# variable_supply_module_v2.net
KiCad netlist of a schematic drawn in EAGLE
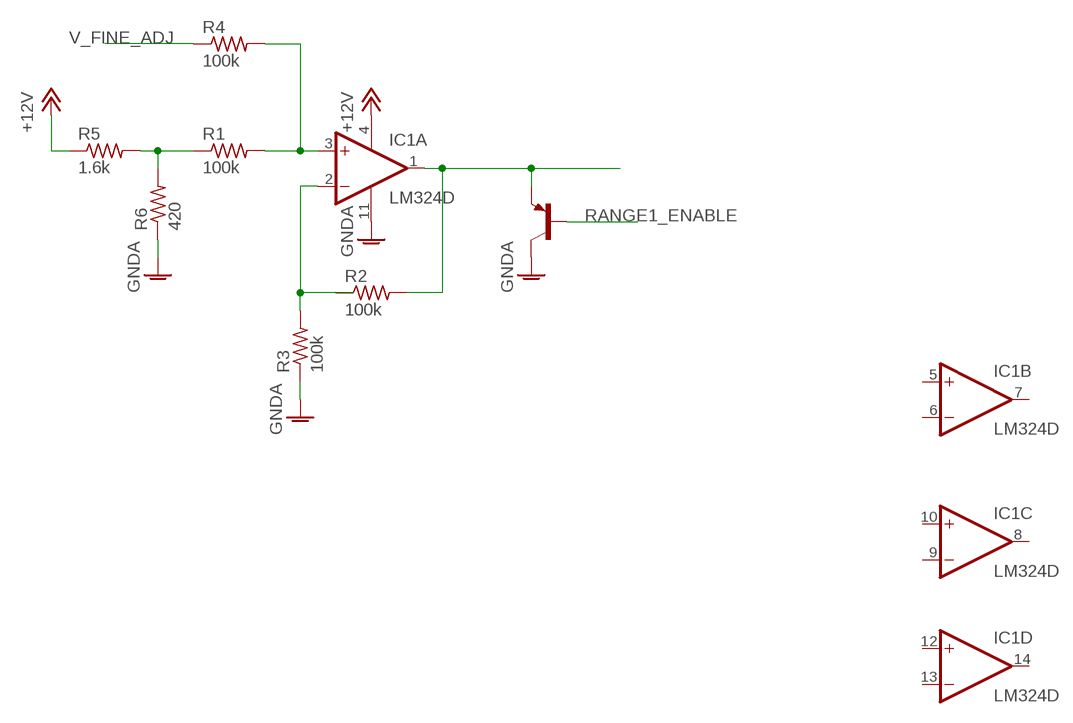
[diagram p0: schematic, sheet 1]

(export (version "E")
  (design (tool "Eeschema 10.0.6"))
  (components
    (comp (ref "IC1")
      (value "LM324D")
      (footprint "eagle-import:SO14")
      (libsource (lib "eagle-import") (part "LM324D"))
    )
    (comp (ref "R1")
      (value "100k")
      (footprint "eagle-import:M0805")
      (libsource (lib "eagle-import") (part "R-US_M0805"))
    )
    (comp (ref "R2")
      (value "100k")
      (footprint "eagle-import:M0805")
      (libsource (lib "eagle-import") (part "R-US_M0805"))
    )
    (comp (ref "R3")
      (value "100k")
      (footprint "eagle-import:M0805")
      (libsource (lib "eagle-import") (part "R-US_M0805"))
    )
    (comp (ref "R4")
      (value "100k")
      (footprint "eagle-import:M0805")
      (libsource (lib "eagle-import") (part "R-US_M0805"))
    )
    (comp (ref "R5")
      (value "1.6k")
      (footprint "eagle-import:M0805")
      (libsource (lib "eagle-import") (part "R-US_M0805"))
    )
    (comp (ref "R6")
      (value "420")
      (footprint "eagle-import:M0805")
      (libsource (lib "eagle-import") (part "R-US_M0805"))
    )
    (comp (ref "T1")
      (value "MMBT3906LT1-PNP-SOT23-BEC")
      (footprint "eagle-import:SOT23-BEC")
      (libsource (lib "eagle-import") (part "-PNP-SOT23-BECMMBT3906LT1"))
    )
  )
  (nets
    (net (code "1") (name "+12V") (class "Default")
      (node (ref "IC1") (pin "4") (pinfunction "V+_4") (pintype "power_in"))
      (node (ref "R5") (pin "1") (pinfunction "1_1") (pintype "passive"))
    )
    (net (code "2") (name "/RANGE1_ENABLE") (class "Default")
      (node (ref "T1") (pin "B") (pinfunction "B_B") (pintype "passive"))
    )
    (net (code "3") (name "/V_FINE_ADJ") (class "Default")
      (node (ref "R4") (pin "1") (pinfunction "1_1") (pintype "passive"))
    )
    (net (code "4") (name "GNDA") (class "Default")
      (node (ref "IC1") (pin "11") (pinfunction "V-_11") (pintype "power_in"))
      (node (ref "R3") (pin "1") (pinfunction "1_1") (pintype "passive"))
      (node (ref "R6") (pin "1") (pinfunction "1_1") (pintype "passive"))
      (node (ref "T1") (pin "C") (pinfunction "C_C") (pintype "passive"))
    )
    (net (code "5") (name "Net-(IC1A-+IN)") (class "Default")
      (node (ref "IC1") (pin "3") (pinfunction "+IN_3") (pintype "input"))
      (node (ref "R1") (pin "2") (pinfunction "2_2") (pintype "passive"))
      (node (ref "R4") (pin "2") (pinfunction "2_2") (pintype "passive"))
    )
    (net (code "6") (name "Net-(IC1A--IN)") (class "Default")
      (node (ref "IC1") (pin "2") (pinfunction "-IN_2") (pintype "input"))
      (node (ref "R3") (pin "2") (pinfunction "2_2") (pintype "passive"))
    )
    (net (code "7") (name "Net-(IC1A-OUT)") (class "Default")
      (node (ref "IC1") (pin "1") (pinfunction "OUT_1") (pintype "output"))
      (node (ref "R2") (pin "2") (pinfunction "2_2") (pintype "passive"))
      (node (ref "T1") (pin "E") (pinfunction "E_E") (pintype "passive"))
    )
    (net (code "8") (name "Net-(R1-Pad1)") (class "Default")
      (node (ref "R1") (pin "1") (pinfunction "1_1") (pintype "passive"))
      (node (ref "R5") (pin "2") (pinfunction "2_2") (pintype "passive"))
      (node (ref "R6") (pin "2") (pinfunction "2_2") (pintype "passive"))
    )
    (net (code "9") (name "unconnected-(IC1B-+IN-Pad5)") (class "Default")
      (node (ref "IC1") (pin "5") (pinfunction "+IN_5") (pintype "input"))
    )
    (net (code "10") (name "unconnected-(IC1B--IN-Pad6)") (class "Default")
      (node (ref "IC1") (pin "6") (pinfunction "-IN_6") (pintype "input"))
    )
    (net (code "11") (name "unconnected-(IC1B-OUT-Pad7)") (class "Default")
      (node (ref "IC1") (pin "7") (pinfunction "OUT_7") (pintype "output"))
    )
    (net (code "12") (name "unconnected-(IC1C-+IN-Pad10)") (class "Default")
      (node (ref "IC1") (pin "10") (pinfunction "+IN_10") (pintype "input"))
    )
    (net (code "13") (name "unconnected-(IC1C--IN-Pad9)") (class "Default")
      (node (ref "IC1") (pin "9") (pinfunction "-IN_9") (pintype "input"))
    )
    (net (code "14") (name "unconnected-(IC1C-OUT-Pad8)") (class "Default")
      (node (ref "IC1") (pin "8") (pinfunction "OUT_8") (pintype "output"))
    )
    (net (code "15") (name "unconnected-(IC1D-+IN-Pad12)") (class "Default")
      (node (ref "IC1") (pin "12") (pinfunction "+IN_12") (pintype "input"))
    )
    (net (code "16") (name "unconnected-(IC1D--IN-Pad13)") (class "Default")
      (node (ref "IC1") (pin "13") (pinfunction "-IN_13") (pintype "input"))
    )
    (net (code "17") (name "unconnected-(IC1D-OUT-Pad14)") (class "Default")
      (node (ref "IC1") (pin "14") (pinfunction "OUT_14") (pintype "output"))
    )
    (net (code "18") (name "unconnected-(R2-Pad1)") (class "Default")
      (node (ref "R2") (pin "1") (pinfunction "1_1") (pintype "passive"))
    )
  )
)
